# TSDM_2017.net
KiCad netlist of a schematic drawn in Altium Designer
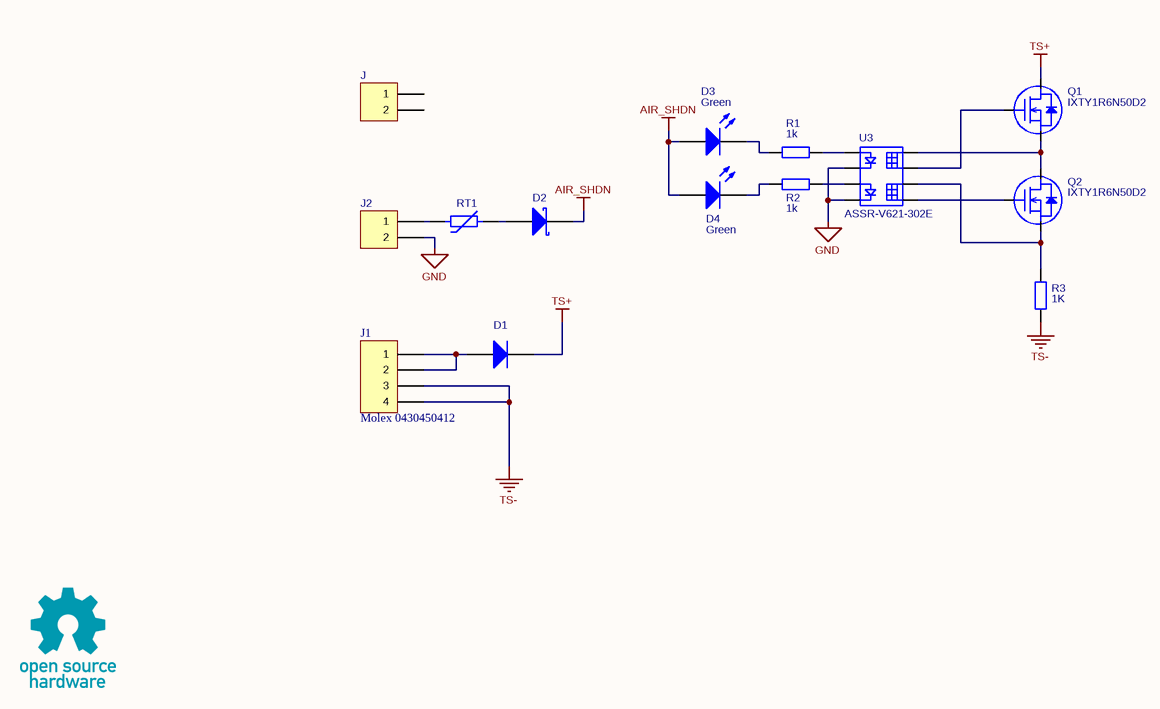
[diagram p0: TSDM_2017.SchDoc]

(export (version "E")
  (design (tool "Eeschema 10.0.6"))
  (components
    (comp (ref "D1")
      (value "STTH1R06")
      (footprint "STMicroelectronics STTH1R06 (SMA)")
      (description "Default Diode")
      (fields (field (name "PUBLISHER") "Altium Limited"))
      (libsource (lib "Miscellaneous Devices") (part "Diode"))
    )
    (comp (ref "D2")
      (value "D Schottky")
      (footprint "NXP PMEG6020AELRX (SOD-123)")
      (description "Schottky Diode")
      (fields (field (name "PUBLISHER") "Altium Limited"))
      (libsource (lib "Miscellaneous Devices") (part "D Schottky"))
    )
    (comp (ref "D3")
      (value "LTST-C193KGKT-5A")
      (footprint "Lite-On LTST-C193K-Series (1608)")
      (description "Typical INFRARED GaAs LED")
      (fields (field (name "PUBLISHER") "Altium Limited"))
      (libsource (lib "Miscellaneous Devices") (part "LED0"))
    )
    (comp (ref "D4")
      (value "LTST-C193KGKT-5A")
      (footprint "Lite-On LTST-C193K-Series (1608)")
      (description "Typical INFRARED GaAs LED")
      (fields (field (name "PUBLISHER") "Altium Limited"))
      (libsource (lib "Miscellaneous Devices") (part "LED0"))
    )
    (comp (ref "J")
      (value "1-770966-0")
      (footprint "TE 1-770966-0")
      (description "Mini-Universal MATE-N-LOK 2-Pin Female Connector")
      (libsource (lib "TSDM_2017") (part "TE 1-770966-0"))
    )
    (comp (ref "J1")
      (value "Molex 0430450412")
      (footprint "MOLEX MICRO-FIT 4POS")
      (description "CONN HEADER VERT 4POS 3MM")
      (libsource (lib "TSDM_2017") (part "Molex 0430450412"))
    )
    (comp (ref "J2")
      (value "~")
      (footprint "TE 2-1445055-2")
      (libsource (lib "TSDM_2017") (part "TE 2-1445055-2"))
    )
    (comp (ref "Q1")
      (value "IXTY1R6N50D2")
      (footprint "IXYS IXTY1R6N50D2 (DPAK)")
      (description "500V Depletion-Mode N-MOSFET")
      (libsource (lib "TSDM_2017") (part "IXYS IXTY1R6N50D2"))
    )
    (comp (ref "Q2")
      (value "IXTY1R6N50D2")
      (footprint "IXYS IXTY1R6N50D2 (DPAK)")
      (description "500V Depletion-Mode N-MOSFET")
      (libsource (lib "TSDM_2017") (part "IXYS IXTY1R6N50D2"))
    )
    (comp (ref "R1")
      (value "1k")
      (footprint "Panasonic ERJ-Series (1608)")
      (description "Resistor")
      (fields (field (name "PUBLISHER") "Altium Limited"))
      (libsource (lib "Miscellaneous Devices") (part "Res2"))
    )
    (comp (ref "R2")
      (value "1k")
      (footprint "Panasonic ERJ-Series (1608)")
      (description "Resistor")
      (fields (field (name "PUBLISHER") "Altium Limited"))
      (libsource (lib "Miscellaneous Devices") (part "Res2"))
    )
    (comp (ref "R3")
      (value "1K")
      (footprint "Ohmite TGH-Series (SOT-227)")
      (description "Resistor")
      (fields (field (name "Comment") "Res2") (field (name "PUBLISHER") "Altium Limited"))
      (libsource (lib "") (part "Res2_1"))
    )
    (comp (ref "RT1")
      (value "~")
      (footprint "Bel Fuse 0ZCM-Series (1608)")
      (description "Thermistor")
      (libsource (lib "TSDM_2017") (part "Thermistor"))
    )
    (comp (ref "U3")
      (value "ASSR-V621-302E")
      (footprint "Avago ASSR-V621-302E (8-SMD)")
      (description "Dual Photovoltaic MOSFET Driver")
      (libsource (lib "TSDM_2017") (part "Avago ASSR-V621-302E_1_1"))
    )
  )
  (nets
    (net (code "1") (name "AIR_SHDN") (class "Default")
      (node (ref "D2") (pin "2") (pinfunction "K_2") (pintype "passive"))
      (node (ref "D3") (pin "1") (pinfunction "A_1") (pintype "passive"))
      (node (ref "D4") (pin "1") (pinfunction "A_1") (pintype "passive"))
    )
    (net (code "2") (name "GND") (class "Default")
      (node (ref "J2") (pin "2") (pinfunction "2_2") (pintype "passive"))
      (node (ref "U3") (pin "2") (pinfunction "CATHODE_2") (pintype "passive"))
      (node (ref "U3") (pin "4") (pinfunction "CATHODE_4") (pintype "passive"))
    )
    (net (code "3") (name "Net-(D1-A)") (class "Default")
      (node (ref "D1") (pin "1") (pinfunction "A_1") (pintype "passive"))
      (node (ref "J1") (pin "1") (pinfunction "1_1") (pintype "passive"))
      (node (ref "J1") (pin "2") (pinfunction "2_2") (pintype "passive"))
    )
    (net (code "4") (name "Net-(D2-A)") (class "Default")
      (node (ref "D2") (pin "1") (pinfunction "A_1") (pintype "passive"))
      (node (ref "RT1") (pin "2") (pinfunction "2_2") (pintype "passive"))
    )
    (net (code "5") (name "Net-(D3-K)") (class "Default")
      (node (ref "D3") (pin "2") (pinfunction "K_2") (pintype "passive"))
      (node (ref "R1") (pin "2") (pinfunction "2_2") (pintype "passive"))
    )
    (net (code "6") (name "Net-(D4-K)") (class "Default")
      (node (ref "D4") (pin "2") (pinfunction "K_2") (pintype "passive"))
      (node (ref "R2") (pin "2") (pinfunction "2_2") (pintype "passive"))
    )
    (net (code "7") (name "Net-(J2-Pad1)") (class "Default")
      (node (ref "J2") (pin "1") (pinfunction "1_1") (pintype "passive"))
      (node (ref "RT1") (pin "1") (pinfunction "1_1") (pintype "passive"))
    )
    (net (code "8") (name "Net-(Q1-GATE)") (class "Default")
      (node (ref "Q1") (pin "1") (pinfunction "GATE_1") (pintype "passive"))
      (node (ref "U3") (pin "7") (pinfunction "OUT-_7") (pintype "power_in"))
    )
    (net (code "9") (name "Net-(Q1-SOURCE)") (class "Default")
      (node (ref "Q1") (pin "3") (pinfunction "SOURCE_3") (pintype "passive"))
      (node (ref "Q2") (pin "4") (pinfunction "DRAIN_4") (pintype "passive"))
      (node (ref "U3") (pin "8") (pinfunction "OUT+_8") (pintype "power_in"))
    )
    (net (code "10") (name "Net-(Q2-GATE)") (class "Default")
      (node (ref "Q2") (pin "1") (pinfunction "GATE_1") (pintype "passive"))
      (node (ref "U3") (pin "5") (pinfunction "OUT-_5") (pintype "power_in"))
    )
    (net (code "11") (name "Net-(Q2-SOURCE)") (class "Default")
      (node (ref "Q2") (pin "3") (pinfunction "SOURCE_3") (pintype "passive"))
      (node (ref "R3") (pin "1") (pinfunction "1_1") (pintype "passive"))
      (node (ref "U3") (pin "6") (pinfunction "OUT+_6") (pintype "power_in"))
    )
    (net (code "12") (name "Net-(R1-Pad1)") (class "Default")
      (node (ref "R1") (pin "1") (pinfunction "1_1") (pintype "passive"))
      (node (ref "U3") (pin "1") (pinfunction "ANODE_1") (pintype "passive"))
    )
    (net (code "13") (name "Net-(R2-Pad1)") (class "Default")
      (node (ref "R2") (pin "1") (pinfunction "1_1") (pintype "passive"))
      (node (ref "U3") (pin "3") (pinfunction "ANODE_3") (pintype "passive"))
    )
    (net (code "14") (name "TS+") (class "Default")
      (node (ref "D1") (pin "2") (pinfunction "K_2") (pintype "passive"))
      (node (ref "Q1") (pin "4") (pinfunction "DRAIN_4") (pintype "passive"))
    )
    (net (code "15") (name "TS-") (class "Default")
      (node (ref "J1") (pin "3") (pinfunction "3_3") (pintype "passive"))
      (node (ref "J1") (pin "4") (pinfunction "4_4") (pintype "passive"))
      (node (ref "R3") (pin "2") (pinfunction "2_2") (pintype "passive"))
    )
    (net (code "16") (name "unconnected-(J-Pad1)") (class "Default")
      (node (ref "J") (pin "1") (pinfunction "1_1") (pintype "passive"))
    )
    (net (code "17") (name "unconnected-(J-Pad2)") (class "Default")
      (node (ref "J") (pin "2") (pinfunction "2_2") (pintype "passive"))
    )
  )
)
